# Nano-CC-EL_0v6_ENP252-17.net
KiCad netlist of a schematic drawn in EAGLE
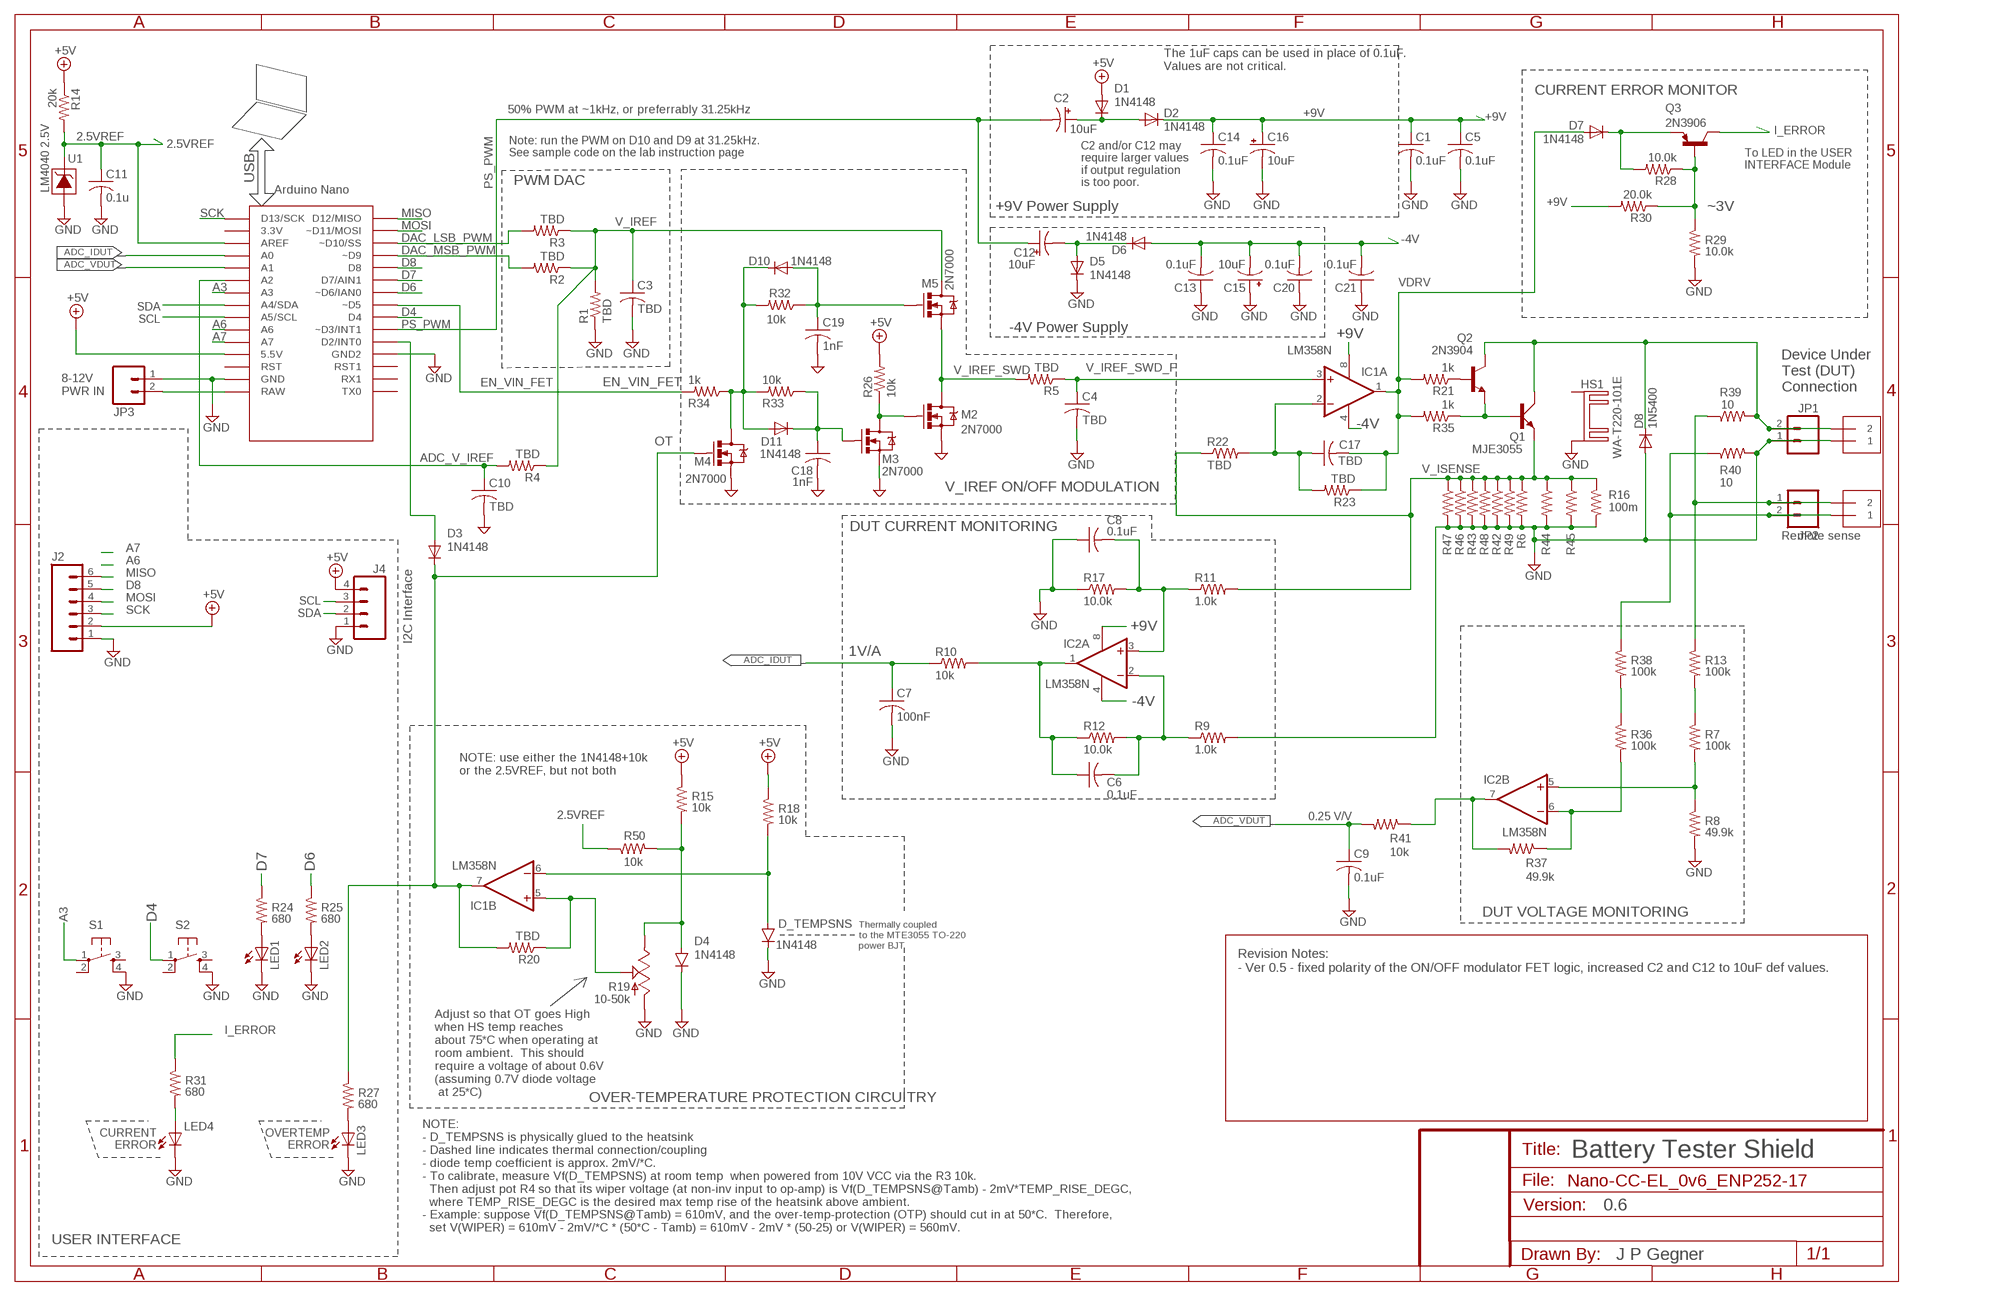
[diagram p0: schematic, sheet 1]

(export (version "E")
  (design (tool "Eeschema 10.0.6"))
  (components
    (comp (ref "C1")
      (value "0.1uF")
      (footprint "eagle-import:C025-025X050")
      (libsource (lib "eagle-import") (part "C-US025-025X050"))
    )
    (comp (ref "C2")
      (value "10uF")
      (footprint "eagle-import:E5-5")
      (libsource (lib "eagle-import") (part "CPOL-USE5-5"))
    )
    (comp (ref "C3")
      (value "TBD")
      (footprint "eagle-import:C025-025X050")
      (libsource (lib "eagle-import") (part "C-US025-025X050"))
    )
    (comp (ref "C4")
      (value "TBD")
      (footprint "eagle-import:C025-025X050")
      (libsource (lib "eagle-import") (part "C-US025-025X050"))
    )
    (comp (ref "C5")
      (value "0.1uF")
      (footprint "eagle-import:C025-025X050")
      (libsource (lib "eagle-import") (part "C-US025-025X050"))
    )
    (comp (ref "C6")
      (value "0.1uF")
      (footprint "eagle-import:C025-025X050")
      (libsource (lib "eagle-import") (part "C-US025-025X050"))
    )
    (comp (ref "C7")
      (value "100nF")
      (footprint "eagle-import:C025-024X044")
      (libsource (lib "eagle-import") (part "C-US025-024X044"))
    )
    (comp (ref "C8")
      (value "0.1uF")
      (footprint "eagle-import:C025-025X050")
      (libsource (lib "eagle-import") (part "C-US025-025X050"))
    )
    (comp (ref "C9")
      (value "0.1uF")
      (footprint "eagle-import:C025-025X050")
      (libsource (lib "eagle-import") (part "C-US025-025X050"))
    )
    (comp (ref "C10")
      (value "TBD")
      (footprint "eagle-import:C025-025X050")
      (libsource (lib "eagle-import") (part "C-US025-025X050"))
    )
    (comp (ref "C11")
      (value "0.1u")
      (footprint "eagle-import:C025-025X050")
      (libsource (lib "eagle-import") (part "C-US025-025X050"))
    )
    (comp (ref "C12")
      (value "10uF")
      (footprint "eagle-import:E5-5")
      (libsource (lib "eagle-import") (part "CPOL-USE5-5"))
    )
    (comp (ref "C13")
      (value "0.1uF")
      (footprint "eagle-import:C025-025X050")
      (libsource (lib "eagle-import") (part "C-US025-025X050"))
    )
    (comp (ref "C14")
      (value "0.1uF")
      (footprint "eagle-import:C025-025X050")
      (libsource (lib "eagle-import") (part "C-US025-025X050"))
    )
    (comp (ref "C15")
      (value "10uF")
      (footprint "eagle-import:E5-5")
      (libsource (lib "eagle-import") (part "CPOL-USE5-5"))
    )
    (comp (ref "C16")
      (value "10uF")
      (footprint "eagle-import:E5-5")
      (libsource (lib "eagle-import") (part "CPOL-USE5-5"))
    )
    (comp (ref "C17")
      (value "TBD")
      (footprint "eagle-import:C025-025X050")
      (libsource (lib "eagle-import") (part "C-US025-025X050"))
    )
    (comp (ref "C18")
      (value "1nF")
      (footprint "eagle-import:C025-025X050")
      (libsource (lib "eagle-import") (part "C-US025-025X050"))
    )
    (comp (ref "C19")
      (value "1nF")
      (footprint "eagle-import:C025-025X050")
      (libsource (lib "eagle-import") (part "C-US025-025X050"))
    )
    (comp (ref "C20")
      (value "0.1uF")
      (footprint "eagle-import:C025-025X050")
      (libsource (lib "eagle-import") (part "C-US025-025X050"))
    )
    (comp (ref "C21")
      (value "0.1uF")
      (footprint "eagle-import:C025-025X050")
      (libsource (lib "eagle-import") (part "C-US025-025X050"))
    )
    (comp (ref "D1")
      (value "1N4148")
      (footprint "eagle-import:0207_2V-D")
      (libsource (lib "eagle-import") (part "1N4148"))
    )
    (comp (ref "D2")
      (value "1N4148")
      (footprint "eagle-import:0207_2V-D")
      (libsource (lib "eagle-import") (part "1N4148"))
    )
    (comp (ref "D3")
      (value "1N4148")
      (footprint "eagle-import:0207_2V-D")
      (libsource (lib "eagle-import") (part "1N4148"))
    )
    (comp (ref "D4")
      (value "1N4148")
      (footprint "eagle-import:0207_2V-D")
      (libsource (lib "eagle-import") (part "ideal_elements_1N4148"))
    )
    (comp (ref "D5")
      (value "1N4148")
      (footprint "eagle-import:0207_2V-D")
      (libsource (lib "eagle-import") (part "1N4148"))
    )
    (comp (ref "D6")
      (value "1N4148")
      (footprint "eagle-import:0207_2V-D")
      (libsource (lib "eagle-import") (part "1N4148"))
    )
    (comp (ref "D7")
      (value "1N4148")
      (footprint "eagle-import:0207_2V-D")
      (libsource (lib "eagle-import") (part "1N4148"))
    )
    (comp (ref "D8")
      (value "1N5400")
      (footprint "eagle-import:DO201-15")
      (libsource (lib "eagle-import") (part "1N5400"))
    )
    (comp (ref "D10")
      (value "1N4148")
      (footprint "eagle-import:0207_2V-D")
      (libsource (lib "eagle-import") (part "1N4148"))
    )
    (comp (ref "D11")
      (value "1N4148")
      (footprint "eagle-import:0207_2V-D")
      (libsource (lib "eagle-import") (part "1N4148"))
    )
    (comp (ref "D_TEMPSNS")
      (value "1N4148")
      (footprint "eagle-import:0207_2V-D")
      (libsource (lib "eagle-import") (part "ideal_elements_1N4148"))
    )
    (comp (ref "HS1")
      (value "WA-T220-101E")
      (footprint "eagle-import:WX-T220-101E")
      (libsource (lib "eagle-import") (part "WA-T220-101E"))
    )
    (comp (ref "IC1")
      (value "LM358N")
      (footprint "eagle-import:DIL08")
      (libsource (lib "eagle-import") (part "LM358N"))
    )
    (comp (ref "IC2")
      (value "LM358N")
      (footprint "eagle-import:DIL08")
      (libsource (lib "eagle-import") (part "LM358N"))
    )
    (comp (ref "J2")
      (value "M06POLAR")
      (footprint "eagle-import:MOLEX-1X6")
      (libsource (lib "eagle-import") (part "M06POLAR"))
    )
    (comp (ref "J4")
      (value "M04LOCK_LONGPADS")
      (footprint "eagle-import:1X04_LOCK_LONGPADS")
      (libsource (lib "eagle-import") (part "M04LOCK_LONGPADS"))
    )
    (comp (ref "JP1")
      (value "M02PTH")
      (footprint "eagle-import:1X02")
      (libsource (lib "eagle-import") (part "M02PTH"))
    )
    (comp (ref "JP2")
      (value "M02PTH")
      (footprint "eagle-import:1X02")
      (libsource (lib "eagle-import") (part "M02PTH"))
    )
    (comp (ref "JP3")
      (value "M02PTH")
      (footprint "eagle-import:1X02")
      (libsource (lib "eagle-import") (part "M02PTH"))
    )
    (comp (ref "JP4")
      (value "1X2-3.5MM")
      (footprint "eagle-import:1X2-3.5MM")
      (libsource (lib "eagle-import") (part "1X2-3.5MM"))
    )
    (comp (ref "JP5")
      (value "1X2-3.5MM")
      (footprint "eagle-import:1X2-3.5MM")
      (libsource (lib "eagle-import") (part "1X2-3.5MM"))
    )
    (comp (ref "LED1")
      (value "LED-3MM-NO_SILK")
      (footprint "eagle-import:LED3MM-NS")
      (libsource (lib "eagle-import") (part "LED-3MM-NO_SILK"))
    )
    (comp (ref "LED2")
      (value "LED-3MM-NO_SILK")
      (footprint "eagle-import:LED3MM-NS")
      (libsource (lib "eagle-import") (part "LED-3MM-NO_SILK"))
    )
    (comp (ref "LED3")
      (value "LED-3MM-NO_SILK")
      (footprint "eagle-import:LED3MM-NS")
      (libsource (lib "eagle-import") (part "LED-3MM-NO_SILK"))
    )
    (comp (ref "LED4")
      (value "LED-3MM-NO_SILK")
      (footprint "eagle-import:LED3MM-NS")
      (libsource (lib "eagle-import") (part "LED-3MM-NO_SILK"))
    )
    (comp (ref "M2")
      (value "2N7000")
      (footprint "eagle-import:TO-92")
      (libsource (lib "eagle-import") (part "MOSFET-NCHANNEL2N7000"))
    )
    (comp (ref "M3")
      (value "2N7000")
      (footprint "eagle-import:TO-92")
      (libsource (lib "eagle-import") (part "MOSFET-NCHANNEL2N7000"))
    )
    (comp (ref "M4")
      (value "2N7000")
      (footprint "eagle-import:TO-92")
      (libsource (lib "eagle-import") (part "MOSFET-NCHANNEL2N7000"))
    )
    (comp (ref "M5")
      (value "2N7000")
      (footprint "eagle-import:TO-92")
      (libsource (lib "eagle-import") (part "MOSFET-NCHANNEL2N7000"))
    )
    (comp (ref "Q1")
      (value "MJE3055")
      (footprint "eagle-import:TO220AV")
      (libsource (lib "eagle-import") (part "MJE3055"))
    )
    (comp (ref "Q2")
      (value "2N3904")
      (footprint "eagle-import:TO92")
      (libsource (lib "eagle-import") (part "2N3904"))
    )
    (comp (ref "Q3")
      (value "2N3906")
      (footprint "eagle-import:TO92")
      (libsource (lib "eagle-import") (part "2N3906"))
    )
    (comp (ref "R1")
      (value "TBD")
      (footprint "eagle-import:0204_7")
      (libsource (lib "eagle-import") (part "R-US_0204/7"))
    )
    (comp (ref "R2")
      (value "TBD")
      (footprint "eagle-import:0204_7")
      (libsource (lib "eagle-import") (part "R-US_0204/7"))
    )
    (comp (ref "R3")
      (value "TBD")
      (footprint "eagle-import:0204_7")
      (libsource (lib "eagle-import") (part "R-US_0204/7"))
    )
    (comp (ref "R4")
      (value "TBD")
      (footprint "eagle-import:0204_7")
      (libsource (lib "eagle-import") (part "R-US_0204/7"))
    )
    (comp (ref "R5")
      (value "TBD")
      (footprint "eagle-import:0204V")
      (libsource (lib "eagle-import") (part "R-US_0204/2V"))
    )
    (comp (ref "R6")
      (value "100m")
      (footprint "eagle-import:0204_7")
      (libsource (lib "eagle-import") (part "R-US_0204/7"))
    )
    (comp (ref "R7")
      (value "100k")
      (footprint "eagle-import:0204_7")
      (libsource (lib "eagle-import") (part "R-US_0204/7"))
    )
    (comp (ref "R8")
      (value "49.9k")
      (footprint "eagle-import:0204_7")
      (libsource (lib "eagle-import") (part "R-US_0204/7"))
    )
    (comp (ref "R9")
      (value "1.0k")
      (footprint "eagle-import:0204_7")
      (libsource (lib "eagle-import") (part "R-US_0204/7"))
    )
    (comp (ref "R10")
      (value "10k")
      (footprint "eagle-import:0204_7")
      (libsource (lib "eagle-import") (part "R-US_0204/7"))
    )
    (comp (ref "R11")
      (value "1.0k")
      (footprint "eagle-import:0204_7")
      (libsource (lib "eagle-import") (part "R-US_0204/7"))
    )
    (comp (ref "R12")
      (value "10.0k")
      (footprint "eagle-import:0204V")
      (libsource (lib "eagle-import") (part "R-US_0204/2V"))
    )
    (comp (ref "R13")
      (value "100k")
      (footprint "eagle-import:0204_7")
      (libsource (lib "eagle-import") (part "R-US_0204/7"))
    )
    (comp (ref "R14")
      (value "20k")
      (footprint "eagle-import:0204_7")
      (libsource (lib "eagle-import") (part "R-US_0204/7"))
    )
    (comp (ref "R15")
      (value "10k")
      (footprint "eagle-import:0204_7")
      (libsource (lib "eagle-import") (part "R-US_0204/7"))
    )
    (comp (ref "R16")
      (value "100m")
      (footprint "eagle-import:0204_7")
      (libsource (lib "eagle-import") (part "R-US_0204/7"))
    )
    (comp (ref "R17")
      (value "10.0k")
      (footprint "eagle-import:0204_7")
      (libsource (lib "eagle-import") (part "R-US_0204/7"))
    )
    (comp (ref "R18")
      (value "10k")
      (footprint "eagle-import:0204_7")
      (libsource (lib "eagle-import") (part "R-US_0204/7"))
    )
    (comp (ref "R19")
      (value "10-50k")
      (footprint "eagle-import:B64Y")
      (libsource (lib "eagle-import") (part "TRIM_US-B64Y"))
    )
    (comp (ref "R20")
      (value "TBD")
      (footprint "eagle-import:0204_7")
      (libsource (lib "eagle-import") (part "R-US_0204/7"))
    )
    (comp (ref "R21")
      (value "1k")
      (footprint "eagle-import:0204_7")
      (libsource (lib "eagle-import") (part "R-US_0204/7"))
    )
    (comp (ref "R22")
      (value "TBD")
      (footprint "eagle-import:0204_7")
      (libsource (lib "eagle-import") (part "R-US_0204/7"))
    )
    (comp (ref "R23")
      (value "TBD")
      (footprint "eagle-import:0204V")
      (libsource (lib "eagle-import") (part "R-US_0204/2V"))
    )
    (comp (ref "R24")
      (value "680")
      (footprint "eagle-import:0204_7")
      (libsource (lib "eagle-import") (part "R-US_0204/7"))
    )
    (comp (ref "R25")
      (value "680")
      (footprint "eagle-import:0204_7")
      (libsource (lib "eagle-import") (part "R-US_0204/7"))
    )
    (comp (ref "R26")
      (value "10k")
      (footprint "eagle-import:0204_7")
      (libsource (lib "eagle-import") (part "R-US_0204/7"))
    )
    (comp (ref "R27")
      (value "680")
      (footprint "eagle-import:0204_7")
      (libsource (lib "eagle-import") (part "R-US_0204/7"))
    )
    (comp (ref "R28")
      (value "10.0k")
      (footprint "eagle-import:0204_7")
      (libsource (lib "eagle-import") (part "R-US_0204/7"))
    )
    (comp (ref "R29")
      (value "10.0k")
      (footprint "eagle-import:0204_7")
      (libsource (lib "eagle-import") (part "R-US_0204/7"))
    )
    (comp (ref "R30")
      (value "20.0k")
      (footprint "eagle-import:0204_7")
      (libsource (lib "eagle-import") (part "R-US_0204/7"))
    )
    (comp (ref "R31")
      (value "680")
      (footprint "eagle-import:0204_7")
      (libsource (lib "eagle-import") (part "R-US_0204/7"))
    )
    (comp (ref "R32")
      (value "10k")
      (footprint "eagle-import:0204_7")
      (libsource (lib "eagle-import") (part "R-US_0204/7"))
    )
    (comp (ref "R33")
      (value "10k")
      (footprint "eagle-import:0204_7")
      (libsource (lib "eagle-import") (part "R-US_0204/7"))
    )
    (comp (ref "R34")
      (value "1k")
      (footprint "eagle-import:0204V")
      (libsource (lib "eagle-import") (part "R-US_0204/2V"))
    )
    (comp (ref "R35")
      (value "1k")
      (footprint "eagle-import:0204_7")
      (libsource (lib "eagle-import") (part "R-US_0204/7"))
    )
    (comp (ref "R36")
      (value "100k")
      (footprint "eagle-import:0204_7")
      (libsource (lib "eagle-import") (part "R-US_0204/7"))
    )
    (comp (ref "R37")
      (value "49.9k")
      (footprint "eagle-import:0204V")
      (libsource (lib "eagle-import") (part "R-US_0204/2V"))
    )
    (comp (ref "R38")
      (value "100k")
      (footprint "eagle-import:0204_7")
      (libsource (lib "eagle-import") (part "R-US_0204/7"))
    )
    (comp (ref "R39")
      (value "10")
      (footprint "eagle-import:0204V")
      (libsource (lib "eagle-import") (part "R-US_0204/2V"))
    )
    (comp (ref "R40")
      (value "10")
      (footprint "eagle-import:0204V")
      (libsource (lib "eagle-import") (part "R-US_0204/2V"))
    )
    (comp (ref "R41")
      (value "10k")
      (footprint "eagle-import:0204_7")
      (libsource (lib "eagle-import") (part "R-US_0204/7"))
    )
    (comp (ref "R42")
      (value "100m")
      (footprint "eagle-import:0204_7")
      (libsource (lib "eagle-import") (part "R-US_0204/7"))
    )
    (comp (ref "R43")
      (value "100m")
      (footprint "eagle-import:0204_7")
      (libsource (lib "eagle-import") (part "R-US_0204/7"))
    )
    (comp (ref "R44")
      (value "100m")
      (footprint "eagle-import:0204_7")
      (libsource (lib "eagle-import") (part "R-US_0204/7"))
    )
    (comp (ref "R45")
      (value "100m")
      (footprint "eagle-import:0204_7")
      (libsource (lib "eagle-import") (part "R-US_0204/7"))
    )
    (comp (ref "R46")
      (value "100m")
      (footprint "eagle-import:0204_7")
      (libsource (lib "eagle-import") (part "R-US_0204/7"))
    )
    (comp (ref "R47")
      (value "100m")
      (footprint "eagle-import:0204_7")
      (libsource (lib "eagle-import") (part "R-US_0204/7"))
    )
    (comp (ref "R48")
      (value "100m")
      (footprint "eagle-import:0204_7")
      (libsource (lib "eagle-import") (part "R-US_0204/7"))
    )
    (comp (ref "R49")
      (value "100m")
      (footprint "eagle-import:0204_7")
      (libsource (lib "eagle-import") (part "R-US_0204/7"))
    )
    (comp (ref "R50")
      (value "10k")
      (footprint "eagle-import:0204_7")
      (libsource (lib "eagle-import") (part "R-US_0204/7"))
    )
    (comp (ref "S1")
      (value "E-SWITCH_TL1105L-F250-Q")
      (footprint "eagle-import:OMRON_B3F-1XX-JPGMOD")
      (libsource (lib "eagle-import") (part "E-SWITCH_TL1105L-F250-Q"))
    )
    (comp (ref "S2")
      (value "E-SWITCH_TL1105L-F250-Q")
      (footprint "eagle-import:OMRON_B3F-1XX-JPGMOD")
      (libsource (lib "eagle-import") (part "E-SWITCH_TL1105L-F250-Q"))
    )
    (comp (ref "U$1")
      (value "NANO")
      (footprint "eagle-import:NANO")
      (libsource (lib "eagle-import") (part "NANO"))
    )
    (comp (ref "U1")
      (value "LM4040 2.5V")
      (footprint "eagle-import:TO92")
      (libsource (lib "eagle-import") (part "LM4040TO92"))
    )
  )
  (nets
    (net (code "1") (name "+5V") (class "Default")
      (node (ref "D1") (pin "A") (pinfunction "A_A") (pintype "passive"))
      (node (ref "J2") (pin "2") (pinfunction "2_2") (pintype "passive"))
      (node (ref "J4") (pin "4") (pinfunction "4_4") (pintype "passive"))
      (node (ref "R14") (pin "1") (pinfunction "1_1") (pintype "passive"))
      (node (ref "R15") (pin "1") (pinfunction "1_1") (pintype "passive"))
      (node (ref "R18") (pin "1") (pinfunction "1_1") (pintype "passive"))
      (node (ref "R26") (pin "2") (pinfunction "2_2") (pintype "passive"))
      (node (ref "U$1") (pin "5V") (pinfunction "5.5V_5V") (pintype "bidirectional"))
    )
    (net (code "2") (name "/+9V") (class "Default")
      (node (ref "C1") (pin "1") (pinfunction "1_1") (pintype "passive"))
      (node (ref "C14") (pin "1") (pinfunction "1_1") (pintype "passive"))
      (node (ref "C16") (pin "+") (pinfunction "+_+") (pintype "passive"))
      (node (ref "C5") (pin "1") (pinfunction "1_1") (pintype "passive"))
      (node (ref "D2") (pin "K") (pinfunction "C_K") (pintype "passive"))
      (node (ref "IC1") (pin "8") (pinfunction "V+_8") (pintype "power_in"))
      (node (ref "IC2") (pin "8") (pinfunction "V+_8") (pintype "power_in"))
      (node (ref "R30") (pin "2") (pinfunction "2_2") (pintype "passive"))
    )
    (net (code "3") (name "/-4V") (class "Default")
      (node (ref "C13") (pin "2") (pinfunction "2_2") (pintype "passive"))
      (node (ref "C15") (pin "-") (pinfunction "-_-") (pintype "passive"))
      (node (ref "C20") (pin "2") (pinfunction "2_2") (pintype "passive"))
      (node (ref "C21") (pin "2") (pinfunction "2_2") (pintype "passive"))
      (node (ref "D6") (pin "A") (pinfunction "A_A") (pintype "passive"))
      (node (ref "IC1") (pin "4") (pinfunction "V-_4") (pintype "power_in"))
      (node (ref "IC2") (pin "4") (pinfunction "V-_4") (pintype "power_in"))
    )
    (net (code "4") (name "/2.5VREF") (class "Default")
      (node (ref "C11") (pin "1") (pinfunction "1_1") (pintype "passive"))
      (node (ref "R14") (pin "2") (pinfunction "2_2") (pintype "passive"))
      (node (ref "R50") (pin "1") (pinfunction "1_1") (pintype "passive"))
      (node (ref "U$1") (pin "AREF") (pinfunction "AREF_AREF") (pintype "bidirectional"))
      (node (ref "U1") (pin "2") (pinfunction "CATHODE_2") (pintype "passive"))
    )
    (net (code "5") (name "/A3") (class "Default")
      (node (ref "S1") (pin "1") (pinfunction "P_1") (pintype "passive"))
      (node (ref "U$1") (pin "A3") (pinfunction "A3_A3") (pintype "bidirectional"))
    )
    (net (code "6") (name "/A6") (class "Default")
      (node (ref "U$1") (pin "A6") (pinfunction "A6_A6") (pintype "bidirectional"))
    )
    (net (code "7") (name "/A7") (class "Default")
      (node (ref "U$1") (pin "A7") (pinfunction "A7_A7") (pintype "bidirectional"))
    )
    (net (code "8") (name "/ADC_IDUT") (class "Default")
      (node (ref "C7") (pin "1") (pinfunction "1_1") (pintype "passive"))
      (node (ref "R10") (pin "1") (pinfunction "1_1") (pintype "passive"))
      (node (ref "U$1") (pin "A0") (pinfunction "A0_A0") (pintype "bidirectional"))
    )
    (net (code "9") (name "/ADC_VDUT") (class "Default")
      (node (ref "C9") (pin "1") (pinfunction "1_1") (pintype "passive"))
      (node (ref "R41") (pin "2") (pinfunction "2_2") (pintype "passive"))
      (node (ref "U$1") (pin "A1") (pinfunction "A1_A1") (pintype "bidirectional"))
    )
    (net (code "10") (name "/ADC_V_IREF") (class "Default")
      (node (ref "C10") (pin "1") (pinfunction "1_1") (pintype "passive"))
      (node (ref "R4") (pin "2") (pinfunction "2_2") (pintype "passive"))
      (node (ref "U$1") (pin "A2") (pinfunction "A2_A2") (pintype "bidirectional"))
    )
    (net (code "11") (name "/D4") (class "Default")
      (node (ref "S2") (pin "1") (pinfunction "P_1") (pintype "passive"))
      (node (ref "U$1") (pin "D4") (pinfunction "D4_D4") (pintype "bidirectional"))
    )
    (net (code "12") (name "/D6") (class "Default")
      (node (ref "R25") (pin "1") (pinfunction "1_1") (pintype "passive"))
      (node (ref "U$1") (pin "D6") (pinfunction "~{D6/IAN0}_D6") (pintype "bidirectional"))
    )
    (net (code "13") (name "/D7") (class "Default")
      (node (ref "R24") (pin "1") (pinfunction "1_1") (pintype "passive"))
      (node (ref "U$1") (pin "D7") (pinfunction "D7/AIN1_D7") (pintype "bidirectional"))
    )
    (net (code "14") (name "/D8") (class "Default")
      (node (ref "J2") (pin "5") (pinfunction "5_5") (pintype "passive"))
      (node (ref "U$1") (pin "D8") (pinfunction "D8_D8") (pintype "bidirectional"))
    )
    (net (code "15") (name "/DAC_LSB_PWM") (class "Default")
      (node (ref "R3") (pin "2") (pinfunction "2_2") (pintype "passive"))
      (node (ref "U$1") (pin "D10") (pinfunction "~{D10/SS}_D10") (pintype "bidirectional"))
    )
    (net (code "16") (name "/DAC_MSB_PWM") (class "Default")
      (node (ref "R2") (pin "2") (pinfunction "2_2") (pintype "passive"))
      (node (ref "U$1") (pin "D9") (pinfunction "~{D9}_D9") (pintype "bidirectional"))
    )
    (net (code "17") (name "/EN_VIN_FET") (class "Default")
      (node (ref "R34") (pin "2") (pinfunction "2_2") (pintype "passive"))
      (node (ref "U$1") (pin "D5") (pinfunction "~{D5}_D5") (pintype "bidirectional"))
    )
    (net (code "18") (name "/I_ERROR") (class "Default")
      (node (ref "Q3") (pin "1") (pinfunction "C_1") (pintype "passive"))
      (node (ref "R31") (pin "1") (pinfunction "1_1") (pintype "passive"))
    )
    (net (code "19") (name "/MISO") (class "Default")
      (node (ref "J2") (pin "6") (pinfunction "6_6") (pintype "passive"))
      (node (ref "U$1") (pin "D12") (pinfunction "D12/MISO_D12") (pintype "bidirectional"))
    )
    (net (code "20") (name "/MOSI") (class "Default")
      (node (ref "J2") (pin "4") (pinfunction "4_4") (pintype "passive"))
      (node (ref "U$1") (pin "D11") (pinfunction "~{D11/MOSI}_D11") (pintype "bidirectional"))
    )
    (net (code "21") (name "/OT") (class "Default")
      (node (ref "D3") (pin "K") (pinfunction "C_K") (pintype "passive"))
      (node (ref "IC1") (pin "7") (pinfunction "OUT_7") (pintype "output"))
      (node (ref "M4") (pin "2") (pinfunction "G_2") (pintype "passive"))
      (node (ref "R20") (pin "2") (pinfunction "2_2") (pintype "passive"))
      (node (ref "R27") (pin "1") (pinfunction "1_1") (pintype "passive"))
    )
    (net (code "22") (name "/PS_PWM") (class "Default")
      (node (ref "C12") (pin "+") (pinfunction "+_+") (pintype "passive"))
      (node (ref "C2") (pin "-") (pinfunction "-_-") (pintype "passive"))
      (node (ref "U$1") (pin "D3") (pinfunction "~{D3/INT1}_D3") (pintype "bidirectional"))
    )
    (net (code "23") (name "/SCK") (class "Default")
      (node (ref "J2") (pin "3") (pinfunction "3_3") (pintype "passive"))
      (node (ref "U$1") (pin "D13") (pinfunction "D13/SCK_D13") (pintype "bidirectional"))
    )
    (net (code "24") (name "/SCL") (class "Default")
      (node (ref "J4") (pin "3") (pinfunction "3_3") (pintype "passive"))
      (node (ref "U$1") (pin "A5") (pinfunction "A5/SCL_A5") (pintype "bidirectional"))
    )
    (net (code "25") (name "/SDA") (class "Default")
      (node (ref "J4") (pin "2") (pinfunction "2_2") (pintype "passive"))
      (node (ref "U$1") (pin "A4") (pinfunction "A4/SDA_A4") (pintype "bidirectional"))
    )
    (net (code "26") (name "/VDRV") (class "Default")
      (node (ref "C17") (pin "2") (pinfunction "2_2") (pintype "passive"))
      (node (ref "D7") (pin "A") (pinfunction "A_A") (pintype "passive"))
      (node (ref "IC1") (pin "1") (pinfunction "OUT_1") (pintype "output"))
      (node (ref "R21") (pin "2") (pinfunction "2_2") (pintype "passive"))
      (node (ref "R23") (pin "1") (pinfunction "1_1") (pintype "passive"))
      (node (ref "R35") (pin "2") (pinfunction "2_2") (pintype "passive"))
    )
    (net (code "27") (name "/V_IREF") (class "Default")
      (node (ref "C3") (pin "1") (pinfunction "1_1") (pintype "passive"))
      (node (ref "M5") (pin "3") (pinfunction "D_3") (pintype "passive"))
      (node (ref "R1") (pin "2") (pinfunction "2_2") (pintype "passive"))
      (node (ref "R2") (pin "1") (pinfunction "1_1") (pintype "passive"))
      (node (ref "R3") (pin "1") (pinfunction "1_1") (pintype "passive"))
      (node (ref "R4") (pin "1") (pinfunction "1_1") (pintype "passive"))
    )
    (net (code "28") (name "/V_IREF_SWD") (class "Default")
      (node (ref "M2") (pin "3") (pinfunction "D_3") (pintype "passive"))
      (node (ref "M5") (pin "1") (pinfunction "S_1") (pintype "passive"))
      (node (ref "R5") (pin "2") (pinfunction "2_2") (pintype "passive"))
    )
    (net (code "29") (name "/V_IREF_SWD_F") (class "Default")
      (node (ref "C4") (pin "1") (pinfunction "1_1") (pintype "passive"))
      (node (ref "IC1") (pin "3") (pinfunction "+IN_3") (pintype "input"))
      (node (ref "R5") (pin "1") (pinfunction "1_1") (pintype "passive"))
    )
    (net (code "30") (name "/V_ISENSE") (class "Default")
      (node (ref "Q1") (pin "E") (pinfunction "E_E") (pintype "passive"))
      (node (ref "R11") (pin "2") (pinfunction "2_2") (pintype "passive"))
      (node (ref "R16") (pin "1") (pinfunction "1_1") (pintype "passive"))
      (node (ref "R22") (pin "1") (pinfunction "1_1") (pintype "passive"))
      (node (ref "R42") (pin "1") (pinfunction "1_1") (pintype "passive"))
      (node (ref "R43") (pin "1") (pinfunction "1_1") (pintype "passive"))
      (node (ref "R44") (pin "1") (pinfunction "1_1") (pintype "passive"))
      (node (ref "R45") (pin "1") (pinfunction "1_1") (pintype "passive"))
      (node (ref "R46") (pin "1") (pinfunction "1_1") (pintype "passive"))
      (node (ref "R47") (pin "1") (pinfunction "1_1") (pintype "passive"))
      (node (ref "R48") (pin "1") (pinfunction "1_1") (pintype "passive"))
      (node (ref "R49") (pin "1") (pinfunction "1_1") (pintype "passive"))
      (node (ref "R6") (pin "1") (pinfunction "1_1") (pintype "passive"))
    )
    (net (code "31") (name "GND") (class "Default")
      (node (ref "C1") (pin "2") (pinfunction "2_2") (pintype "passive"))
      (node (ref "C10") (pin "2") (pinfunction "2_2") (pintype "passive"))
      (node (ref "C11") (pin "2") (pinfunction "2_2") (pintype "passive"))
      (node (ref "C13") (pin "1") (pinfunction "1_1") (pintype "passive"))
      (node (ref "C14") (pin "2") (pinfunction "2_2") (pintype "passive"))
      (node (ref "C15") (pin "+") (pinfunction "+_+") (pintype "passive"))
      (node (ref "C16") (pin "-") (pinfunction "-_-") (pintype "passive"))
      (node (ref "C18") (pin "2") (pinfunction "2_2") (pintype "passive"))
      (node (ref "C19") (pin "2") (pinfunction "2_2") (pintype "passive"))
      (node (ref "C20") (pin "1") (pinfunction "1_1") (pintype "passive"))
      (node (ref "C21") (pin "1") (pinfunction "1_1") (pintype "passive"))
      (node (ref "C3") (pin "2") (pinfunction "2_2") (pintype "passive"))
      (node (ref "C4") (pin "2") (pinfunction "2_2") (pintype "passive"))
      (node (ref "C5") (pin "2") (pinfunction "2_2") (pintype "passive"))
      (node (ref "C7") (pin "2") (pinfunction "2_2") (pintype "passive"))
      (node (ref "C8") (pin "1") (pinfunction "1_1") (pintype "passive"))
      (node (ref "C9") (pin "2") (pinfunction "2_2") (pintype "passive"))
      (node (ref "D4") (pin "K") (pinfunction "C_K") (pintype "passive"))
      (node (ref "D5") (pin "K") (pinfunction "C_K") (pintype "passive"))
      (node (ref "D8") (pin "A") (pinfunction "A_A") (pintype "passive"))
      (node (ref "D_TEMPSNS") (pin "K") (pinfunction "C_K") (pintype "passive"))
      (node (ref "HS1") (pin "K2") (pinfunction "K_K2") (pintype "passive"))
      (node (ref "J2") (pin "1") (pinfunction "1_1") (pintype "passive"))
      (node (ref "J4") (pin "1") (pinfunction "1_1") (pintype "passive"))
      (node (ref "JP1") (pin "1") (pinfunction "1_1") (pintype "passive"))
      (node (ref "JP3") (pin "1") (pinfunction "1_1") (pintype "passive"))
      (node (ref "JP5") (pin "1") (pinfunction "1_1") (pintype "passive"))
      (node (ref "LED1") (pin "K") (pinfunction "C_K") (pintype "passive"))
      (node (ref "LED2") (pin "K") (pinfunction "C_K") (pintype "passive"))
      (node (ref "LED3") (pin "K") (pinfunction "C_K") (pintype "passive"))
      (node (ref "LED4") (pin "K") (pinfunction "C_K") (pintype "passive"))
      (node (ref "M2") (pin "1") (pinfunction "S_1") (pintype "passive"))
      (node (ref "M3") (pin "1") (pinfunction "S_1") (pintype "passive"))
      (node (ref "M4") (pin "1") (pinfunction "S_1") (pintype "passive"))
      (node (ref "R1") (pin "1") (pinfunction "1_1") (pintype "passive"))
      (node (ref "R16") (pin "2") (pinfunction "2_2") (pintype "passive"))
      (node (ref "R17") (pin "1") (pinfunction "1_1") (pintype "passive"))
      (node (ref "R19") (pin "A") (pinfunction "A_A") (pintype "passive"))
      (node (ref "R29") (pin "2") (pinfunction "2_2") (pintype "passive"))
      (node (ref "R40") (pin "2") (pinfunction "2_2") (pintype "passive"))
      (node (ref "R42") (pin "2") (pinfunction "2_2") (pintype "passive"))
      (node (ref "R43") (pin "2") (pinfunction "2_2") (pintype "passive"))
      (node (ref "R44") (pin "2") (pinfunction "2_2") (pintype "passive"))
      (node (ref "R45") (pin "2") (pinfunction "2_2") (pintype "passive"))
      (node (ref "R46") (pin "2") (pinfunction "2_2") (pintype "passive"))
      (node (ref "R47") (pin "2") (pinfunction "2_2") (pintype "passive"))
      (node (ref "R48") (pin "2") (pinfunction "2_2") (pintype "passive"))
      (node (ref "R49") (pin "2") (pinfunction "2_2") (pintype "passive"))
      (node (ref "R6") (pin "2") (pinfunction "2_2") (pintype "passive"))
      (node (ref "R8") (pin "2") (pinfunction "2_2") (pintype "passive"))
      (node (ref "R9") (pin "2") (pinfunction "2_2") (pintype "passive"))
      (node (ref "S1") (pin "4") (pinfunction "S1_4") (pintype "passive"))
      (node (ref "S2") (pin "4") (pinfunction "S1_4") (pintype "passive"))
      (node (ref "U$1") (pin "GND") (pinfunction "GND_GND") (pintype "bidirectional"))
      (node (ref "U$1") (pin "GND1") (pinfunction "GND2_GND1") (pintype "bidirectional"))
      (node (ref "U1") (pin "3") (pinfunction "ANODE_3") (pintype "passive"))
    )
    (net (code "32") (name "Net-(D1-C)") (class "Default")
      (node (ref "C2") (pin "+") (pinfunction "+_+") (pintype "passive"))
      (node (ref "D1") (pin "K") (pinfunction "C_K") (pintype "passive"))
      (node (ref "D2") (pin "A") (pinfunction "A_A") (pintype "passive"))
    )
    (net (code "33") (name "Net-(D4-PadA)") (class "Default")
      (node (ref "D4") (pin "A") (pinfunction "A_A") (pintype "passive"))
      (node (ref "R15") (pin "2") (pinfunction "2_2") (pintype "passive"))
      (node (ref "R19") (pin "E") (pinfunction "E_E") (pintype "passive"))
      (node (ref "R50") (pin "2") (pinfunction "2_2") (pintype "passive"))
    )
    (net (code "34") (name "Net-(D6-C)") (class "Default")
      (node (ref "C12") (pin "-") (pinfunction "-_-") (pintype "passive"))
      (node (ref "D5") (pin "A") (pinfunction "A_A") (pintype "passive"))
      (node (ref "D6") (pin "K") (pinfunction "C_K") (pintype "passive"))
    )
    (net (code "35") (name "Net-(D7-C)") (class "Default")
      (node (ref "D7") (pin "K") (pinfunction "C_K") (pintype "passive"))
      (node (ref "Q3") (pin "3") (pinfunction "E_3") (pintype "passive"))
      (node (ref "R28") (pin "2") (pinfunction "2_2") (pintype "passive"))
    )
    (net (code "36") (name "Net-(D10-C)") (class "Default")
      (node (ref "D10") (pin "K") (pinfunction "C_K") (pintype "passive"))
      (node (ref "D11") (pin "A") (pinfunction "A_A") (pintype "passive"))
      (node (ref "M4") (pin "3") (pinfunction "D_3") (pintype "passive"))
      (node (ref "R32") (pin "2") (pinfunction "2_2") (pintype "passive"))
      (node (ref "R33") (pin "2") (pinfunction "2_2") (pintype "passive"))
      (node (ref "R34") (pin "1") (pinfunction "1_1") (pintype "passive"))
    )
    (net (code "37") (name "Net-(D11-C)") (class "Default")
      (node (ref "C18") (pin "1") (pinfunction "1_1") (pintype "passive"))
      (node (ref "D11") (pin "K") (pinfunction "C_K") (pintype "passive"))
      (node (ref "M3") (pin "2") (pinfunction "G_2") (pintype "passive"))
      (node (ref "R33") (pin "1") (pinfunction "1_1") (pintype "passive"))
    )
    (net (code "38") (name "Net-(IC1A--IN)") (class "Default")
      (node (ref "C17") (pin "1") (pinfunction "1_1") (pintype "passive"))
      (node (ref "IC1") (pin "2") (pinfunction "-IN_2") (pintype "input"))
      (node (ref "R22") (pin "2") (pinfunction "2_2") (pintype "passive"))
      (node (ref "R23") (pin "2") (pinfunction "2_2") (pintype "passive"))
    )
    (net (code "39") (name "Net-(IC1B-+IN)") (class "Default")
      (node (ref "IC1") (pin "5") (pinfunction "+IN_5") (pintype "input"))
      (node (ref "R19") (pin "S") (pinfunction "S_S") (pintype "passive"))
      (node (ref "R20") (pin "1") (pinfunction "1_1") (pintype "passive"))
    )
    (net (code "40") (name "Net-(IC1B--IN)") (class "Default")
      (node (ref "D_TEMPSNS") (pin "A") (pinfunction "A_A") (pintype "passive"))
      (node (ref "IC1") (pin "6") (pinfunction "-IN_6") (pintype "input"))
      (node (ref "R18") (pin "2") (pinfunction "2_2") (pintype "passive"))
    )
    (net (code "41") (name "Net-(IC2A-+IN)") (class "Default")
      (node (ref "C8") (pin "2") (pinfunction "2_2") (pintype "passive"))
      (node (ref "IC2") (pin "3") (pinfunction "+IN_3") (pintype "input"))
      (node (ref "R11") (pin "1") (pinfunction "1_1") (pintype "passive"))
      (node (ref "R17") (pin "2") (pinfunction "2_2") (pintype "passive"))
    )
    (net (code "42") (name "Net-(IC2A--IN)") (class "Default")
      (node (ref "C6") (pin "2") (pinfunction "2_2") (pintype "passive"))
      (node (ref "IC2") (pin "2") (pinfunction "-IN_2") (pintype "input"))
      (node (ref "R12") (pin "2") (pinfunction "2_2") (pintype "passive"))
      (node (ref "R9") (pin "1") (pinfunction "1_1") (pintype "passive"))
    )
    (net (code "43") (name "Net-(IC2A-OUT)") (class "Default")
      (node (ref "C6") (pin "1") (pinfunction "1_1") (pintype "passive"))
      (node (ref "IC2") (pin "1") (pinfunction "OUT_1") (pintype "output"))
      (node (ref "R10") (pin "2") (pinfunction "2_2") (pintype "passive"))
      (node (ref "R12") (pin "1") (pinfunction "1_1") (pintype "passive"))
    )
    (net (code "44") (name "Net-(IC2B-+IN)") (class "Default")
      (node (ref "IC2") (pin "5") (pinfunction "+IN_5") (pintype "input"))
      (node (ref "R7") (pin "2") (pinfunction "2_2") (pintype "passive"))
      (node (ref "R8") (pin "1") (pinfunction "1_1") (pintype "passive"))
    )
    (net (code "45") (name "Net-(IC2B--IN)") (class "Default")
      (node (ref "IC2") (pin "6") (pinfunction "-IN_6") (pintype "input"))
      (node (ref "R36") (pin "2") (pinfunction "2_2") (pintype "passive"))
      (node (ref "R37") (pin "1") (pinfunction "1_1") (pintype "passive"))
    )
    (net (code "46") (name "Net-(IC2B-OUT)") (class "Default")
      (node (ref "IC2") (pin "7") (pinfunction "OUT_7") (pintype "output"))
      (node (ref "R37") (pin "2") (pinfunction "2_2") (pintype "passive"))
      (node (ref "R41") (pin "1") (pinfunction "1_1") (pintype "passive"))
    )
    (net (code "47") (name "Net-(JP2-Pad1)") (class "Default")
      (node (ref "JP2") (pin "1") (pinfunction "1_1") (pintype "passive"))
      (node (ref "JP4") (pin "2") (pinfunction "2_2") (pintype "passive"))
      (node (ref "R13") (pin "1") (pinfunction "1_1") (pintype "passive"))
      (node (ref "R39") (pin "1") (pinfunction "1_1") (pintype "passive"))
    )
    (net (code "48") (name "Net-(JP2-Pad2)") (class "Default")
      (node (ref "JP2") (pin "2") (pinfunction "2_2") (pintype "passive"))
      (node (ref "JP4") (pin "1") (pinfunction "1_1") (pintype "passive"))
      (node (ref "R38") (pin "1") (pinfunction "1_1") (pintype "passive"))
      (node (ref "R40") (pin "1") (pinfunction "1_1") (pintype "passive"))
    )
    (net (code "49") (name "Net-(JP3-Pad2)") (class "Default")
      (node (ref "JP3") (pin "2") (pinfunction "2_2") (pintype "passive"))
      (node (ref "U$1") (pin "RAW") (pinfunction "RAW_RAW") (pintype "bidirectional"))
    )
    (net (code "50") (name "Net-(LED1-PadA)") (class "Default")
      (node (ref "LED1") (pin "A") (pinfunction "A_A") (pintype "passive"))
      (node (ref "R24") (pin "2") (pinfunction "2_2") (pintype "passive"))
    )
    (net (code "51") (name "Net-(LED2-PadA)") (class "Default")
      (node (ref "LED2") (pin "A") (pinfunction "A_A") (pintype "passive"))
      (node (ref "R25") (pin "2") (pinfunction "2_2") (pintype "passive"))
    )
    (net (code "52") (name "Net-(LED3-PadA)") (class "Default")
      (node (ref "LED3") (pin "A") (pinfunction "A_A") (pintype "passive"))
      (node (ref "R27") (pin "2") (pinfunction "2_2") (pintype "passive"))
    )
    (net (code "53") (name "Net-(LED4-PadA)") (class "Default")
      (node (ref "LED4") (pin "A") (pinfunction "A_A") (pintype "passive"))
      (node (ref "R31") (pin "2") (pinfunction "2_2") (pintype "passive"))
    )
    (net (code "54") (name "Net-(M2-G)") (class "Default")
      (node (ref "M2") (pin "2") (pinfunction "G_2") (pintype "passive"))
      (node (ref "M3") (pin "3") (pinfunction "D_3") (pintype "passive"))
      (node (ref "R26") (pin "1") (pinfunction "1_1") (pintype "passive"))
    )
    (net (code "55") (name "Net-(M5-G)") (class "Default")
      (node (ref "C19") (pin "1") (pinfunction "1_1") (pintype "passive"))
      (node (ref "D10") (pin "A") (pinfunction "A_A") (pintype "passive"))
      (node (ref "M5") (pin "2") (pinfunction "G_2") (pintype "passive"))
      (node (ref "R32") (pin "1") (pinfunction "1_1") (pintype "passive"))
    )
    (net (code "56") (name "Net-(Q2-B)") (class "Default")
      (node (ref "Q2") (pin "2") (pinfunction "B_2") (pintype "passive"))
      (node (ref "R21") (pin "1") (pinfunction "1_1") (pintype "passive"))
    )
    (net (code "57") (name "Net-(Q2-C)") (class "Default")
      (node (ref "D8") (pin "C") (pinfunction "C_C") (pintype "passive"))
      (node (ref "JP1") (pin "2") (pinfunction "2_2") (pintype "passive"))
      (node (ref "JP5") (pin "2") (pinfunction "2_2") (pintype "passive"))
      (node (ref "Q1") (pin "C") (pinfunction "C_C") (pintype "passive"))
      (node (ref "Q2") (pin "1") (pinfunction "C_1") (pintype "passive"))
      (node (ref "R39") (pin "2") (pinfunction "2_2") (pintype "passive"))
    )
    (net (code "58") (name "Net-(Q2-E)") (class "Default")
      (node (ref "Q1") (pin "B") (pinfunction "B_B") (pintype "passive"))
      (node (ref "Q2") (pin "3") (pinfunction "E_3") (pintype "passive"))
      (node (ref "R35") (pin "1") (pinfunction "1_1") (pintype "passive"))
    )
    (net (code "59") (name "Net-(Q3-B)") (class "Default")
      (node (ref "Q3") (pin "2") (pinfunction "B_2") (pintype "passive"))
      (node (ref "R28") (pin "1") (pinfunction "1_1") (pintype "passive"))
      (node (ref "R29") (pin "1") (pinfunction "1_1") (pintype "passive"))
      (node (ref "R30") (pin "1") (pinfunction "1_1") (pintype "passive"))
    )
    (net (code "60") (name "Net-(R13-Pad2)") (class "Default")
      (node (ref "R13") (pin "2") (pinfunction "2_2") (pintype "passive"))
      (node (ref "R7") (pin "1") (pinfunction "1_1") (pintype "passive"))
    )
    (net (code "61") (name "Net-(R36-Pad1)") (class "Default")
      (node (ref "R36") (pin "1") (pinfunction "1_1") (pintype "passive"))
      (node (ref "R38") (pin "2") (pinfunction "2_2") (pintype "passive"))
    )
    (net (code "62") (name "Net-(U$1-D2{slash}INT0)") (class "Default")
      (node (ref "D3") (pin "A") (pinfunction "A_A") (pintype "passive"))
      (node (ref "U$1") (pin "D2") (pinfunction "D2/INT0_D2") (pintype "bidirectional"))
    )
    (net (code "63") (name "unconnected-(HS1-K-PadK1)") (class "Default")
      (node (ref "HS1") (pin "K1") (pinfunction "K_K1") (pintype "passive"))
    )
    (net (code "64") (name "unconnected-(S1-P1-Pad2)") (class "Default")
      (node (ref "S1") (pin "2") (pinfunction "P1_2") (pintype "passive"))
    )
    (net (code "65") (name "unconnected-(S1-S-Pad3)") (class "Default")
      (node (ref "S1") (pin "3") (pinfunction "S_3") (pintype "passive"))
    )
    (net (code "66") (name "unconnected-(S2-P1-Pad2)") (class "Default")
      (node (ref "S2") (pin "2") (pinfunction "P1_2") (pintype "passive"))
    )
    (net (code "67") (name "unconnected-(S2-S-Pad3)") (class "Default")
      (node (ref "S2") (pin "3") (pinfunction "S_3") (pintype "passive"))
    )
    (net (code "68") (name "unconnected-(U$1-Pad3.3V)") (class "Default")
      (node (ref "U$1") (pin "3.3V") (pinfunction "3.3V_3.3V") (pintype "bidirectional"))
    )
    (net (code "69") (name "unconnected-(U$1-PadICSP1)") (class "Default")
      (node (ref "U$1") (pin "ICSP1") (pinfunction "ICSP1_ICSP1") (pintype "bidirectional"))
    )
    (net (code "70") (name "unconnected-(U$1-PadICSP2)") (class "Default")
      (node (ref "U$1") (pin "ICSP2") (pinfunction "ICSP2_ICSP2") (pintype "bidirectional"))
    )
    (net (code "71") (name "unconnected-(U$1-PadICSP3)") (class "Default")
      (node (ref "U$1") (pin "ICSP3") (pinfunction "ICSP3_ICSP3") (pintype "bidirectional"))
    )
    (net (code "72") (name "unconnected-(U$1-PadICSP4)") (class "Default")
      (node (ref "U$1") (pin "ICSP4") (pinfunction "ICSP4_ICSP4") (pintype "bidirectional"))
    )
    (net (code "73") (name "unconnected-(U$1-PadICSP5)") (class "Default")
      (node (ref "U$1") (pin "ICSP5") (pinfunction "ICSP5_ICSP5") (pintype "bidirectional"))
    )
    (net (code "74") (name "unconnected-(U$1-PadICSP6)") (class "Default")
      (node (ref "U$1") (pin "ICSP6") (pinfunction "ICSP6_ICSP6") (pintype "bidirectional"))
    )
    (net (code "75") (name "unconnected-(U$1-PadRST)") (class "Default")
      (node (ref "U$1") (pin "RST") (pinfunction "RST_RST") (pintype "bidirectional"))
    )
    (net (code "76") (name "unconnected-(U$1-PadRST1)") (class "Default")
      (node (ref "U$1") (pin "RST1") (pinfunction "RST1_RST1") (pintype "bidirectional"))
    )
    (net (code "77") (name "unconnected-(U$1-PadRX1)") (class "Default")
      (node (ref "U$1") (pin "RX1") (pinfunction "RX1_RX1") (pintype "bidirectional"))
    )
    (net (code "78") (name "unconnected-(U$1-PadTX0)") (class "Default")
      (node (ref "U$1") (pin "TX0") (pinfunction "TX0_TX0") (pintype "bidirectional"))
    )
  )
)
